# QColor-V1.net
KiCad netlist of a schematic drawn in EAGLE
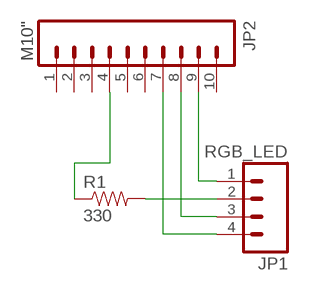
[diagram p0: schematic, sheet 1]

(export (version "E")
  (design (tool "Eeschema 10.0.6"))
  (components
    (comp (ref "JP1")
      (value "RGB_LED")
      (footprint "eagle-import:1X04")
      (libsource (lib "eagle-import") (part "M04PTH"))
    )
    (comp (ref "JP2")
      (value "M10\"")
      (footprint "eagle-import:1X10")
      (libsource (lib "eagle-import") (part "M10{dblquote}"))
    )
    (comp (ref "R1")
      (value "330")
      (footprint "eagle-import:AXIAL-0.3")
      (libsource (lib "eagle-import") (part "RESISTORAXIAL-0.3"))
    )
  )
  (nets
    (net (code "1") (name "Net-(JP1-Pad1)") (class "Default")
      (node (ref "JP1") (pin "1") (pinfunction "1_1") (pintype "passive"))
      (node (ref "JP2") (pin "9") (pinfunction "9_9") (pintype "passive"))
    )
    (net (code "2") (name "Net-(JP1-Pad3)") (class "Default")
      (node (ref "JP1") (pin "3") (pinfunction "3_3") (pintype "passive"))
      (node (ref "JP2") (pin "8") (pinfunction "8_8") (pintype "passive"))
    )
    (net (code "3") (name "Net-(JP1-Pad4)") (class "Default")
      (node (ref "JP1") (pin "4") (pinfunction "4_4") (pintype "passive"))
      (node (ref "JP2") (pin "7") (pinfunction "7_7") (pintype "passive"))
    )
    (net (code "4") (name "Net-(R1-1)") (class "Default")
      (node (ref "JP2") (pin "4") (pinfunction "4_4") (pintype "passive"))
      (node (ref "R1") (pin "P$1") (pinfunction "1_P$1") (pintype "passive"))
    )
    (net (code "5") (name "Net-(R1-2)") (class "Default")
      (node (ref "JP1") (pin "2") (pinfunction "2_2") (pintype "passive"))
      (node (ref "R1") (pin "P$2") (pinfunction "2_P$2") (pintype "passive"))
    )
    (net (code "6") (name "unconnected-(JP2-Pad1)") (class "Default")
      (node (ref "JP2") (pin "1") (pinfunction "1_1") (pintype "passive"))
    )
    (net (code "7") (name "unconnected-(JP2-Pad2)") (class "Default")
      (node (ref "JP2") (pin "2") (pinfunction "2_2") (pintype "passive"))
    )
    (net (code "8") (name "unconnected-(JP2-Pad3)") (class "Default")
      (node (ref "JP2") (pin "3") (pinfunction "3_3") (pintype "passive"))
    )
    (net (code "9") (name "unconnected-(JP2-Pad5)") (class "Default")
      (node (ref "JP2") (pin "5") (pinfunction "5_5") (pintype "passive"))
    )
    (net (code "10") (name "unconnected-(JP2-Pad6)") (class "Default")
      (node (ref "JP2") (pin "6") (pinfunction "6_6") (pintype "passive"))
    )
    (net (code "11") (name "unconnected-(JP2-Pad10)") (class "Default")
      (node (ref "JP2") (pin "10") (pinfunction "10_10") (pintype "passive"))
    )
  )
)
